# microcontroller.net
KiCad netlist of a schematic drawn in Altium Designer
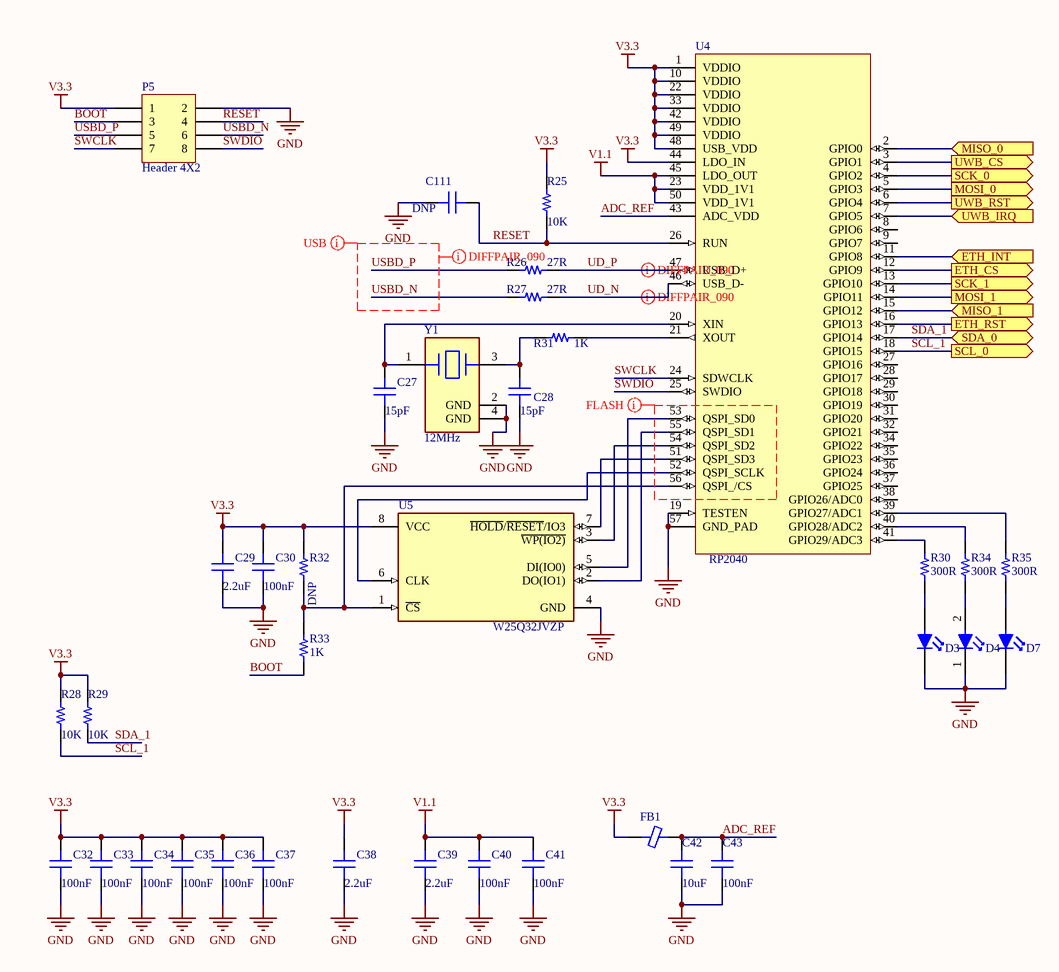
[diagram p0: microcontroller.SchDoc]

(export (version "E")
  (design (tool "Eeschema 10.0.6"))
  (components
    (comp (ref "C27")
      (value "15pF")
      (footprint "CAP 0603_1608")
      (description "SMT Capacitor")
      (fields (field (name "MF") "Murata") (field (name "MP") "GRM1885C1H150JA01J"))
      (libsource (lib "Capacitor") (part "Capacitor"))
    )
    (comp (ref "C28")
      (value "15pF")
      (footprint "CAP 0603_1608")
      (description "SMT Capacitor")
      (fields (field (name "MF") "Murata") (field (name "MP") "GRM1885C1H150JA01J"))
      (libsource (lib "Capacitor") (part "Capacitor"))
    )
    (comp (ref "C29")
      (value "2.2uF")
      (footprint "CAP 0603_1608")
      (description "SMT Capacitor")
      (fields (field (name "MF") "Samsung") (field (name "MP") "CL10A225KP8NNNC"))
      (libsource (lib "Capacitor") (part "Capacitor"))
    )
    (comp (ref "C30")
      (value "100nF")
      (footprint "CAP 0603_1608")
      (description "SMT Capacitor")
      (fields (field (name "MF") "TDK") (field (name "MP") "CGA3E2X7R1E104K080AA"))
      (libsource (lib "Capacitor") (part "Capacitor"))
    )
    (comp (ref "C32")
      (value "100nF")
      (footprint "CAP 0603_1608")
      (description "SMT Capacitor")
      (fields (field (name "MF") "TDK") (field (name "MP") "CGA3E2X7R1E104K080AA"))
      (libsource (lib "Capacitor") (part "Capacitor"))
    )
    (comp (ref "C33")
      (value "100nF")
      (footprint "CAP 0603_1608")
      (description "SMT Capacitor")
      (fields (field (name "MF") "TDK") (field (name "MP") "CGA3E2X7R1E104K080AA"))
      (libsource (lib "Capacitor") (part "Capacitor"))
    )
    (comp (ref "C34")
      (value "100nF")
      (footprint "CAP 0603_1608")
      (description "SMT Capacitor")
      (fields (field (name "MF") "TDK") (field (name "MP") "CGA3E2X7R1E104K080AA"))
      (libsource (lib "Capacitor") (part "Capacitor"))
    )
    (comp (ref "C35")
      (value "100nF")
      (footprint "CAP 0603_1608")
      (description "SMT Capacitor")
      (fields (field (name "MF") "TDK") (field (name "MP") "CGA3E2X7R1E104K080AA"))
      (libsource (lib "Capacitor") (part "Capacitor"))
    )
    (comp (ref "C36")
      (value "100nF")
      (footprint "CAP 0603_1608")
      (description "SMT Capacitor")
      (fields (field (name "MF") "TDK") (field (name "MP") "CGA3E2X7R1E104K080AA"))
      (libsource (lib "Capacitor") (part "Capacitor"))
    )
    (comp (ref "C37")
      (value "100nF")
      (footprint "CAP 0603_1608")
      (description "SMT Capacitor")
      (fields (field (name "MF") "TDK") (field (name "MP") "CGA3E2X7R1E104K080AA"))
      (libsource (lib "Capacitor") (part "Capacitor"))
    )
    (comp (ref "C38")
      (value "2.2uF")
      (footprint "CAP 0603_1608")
      (description "SMT Capacitor")
      (fields (field (name "MF") "Samsung") (field (name "MP") "CL10A225KP8NNNC"))
      (libsource (lib "Capacitor") (part "Capacitor"))
    )
    (comp (ref "C39")
      (value "2.2uF")
      (footprint "CAP 0603_1608")
      (description "SMT Capacitor")
      (fields (field (name "MF") "Samsung") (field (name "MP") "CL10A225KP8NNNC"))
      (libsource (lib "Capacitor") (part "Capacitor"))
    )
    (comp (ref "C40")
      (value "100nF")
      (footprint "CAP 0603_1608")
      (description "SMT Capacitor")
      (fields (field (name "MF") "TDK") (field (name "MP") "CGA3E2X7R1E104K080AA"))
      (libsource (lib "Capacitor") (part "Capacitor"))
    )
    (comp (ref "C41")
      (value "100nF")
      (footprint "CAP 0603_1608")
      (description "SMT Capacitor")
      (fields (field (name "MF") "TDK") (field (name "MP") "CGA3E2X7R1E104K080AA"))
      (libsource (lib "Capacitor") (part "Capacitor"))
    )
    (comp (ref "C42")
      (value "10uF")
      (footprint "CAP 0603_1608")
      (description "SMT Capacitor")
      (fields (field (name "MF") "Murata") (field (name "MP") "GRM188R61C106MAALD"))
      (libsource (lib "Capacitor") (part "Capacitor"))
    )
    (comp (ref "C43")
      (value "100nF")
      (footprint "CAP 0603_1608")
      (description "SMT Capacitor")
      (fields (field (name "MF") "TDK") (field (name "MP") "CGA3E2X7R1E104K080AA"))
      (libsource (lib "Capacitor") (part "Capacitor"))
    )
    (comp (ref "C111")
      (value "DNP")
      (footprint "CAP 0603_1608")
      (description "SMT Capacitor")
      (fields (field (name "MP") "C0603C104K4PACTU"))
      (libsource (lib "Capacitor") (part "Capacitor"))
    )
    (comp (ref "D3")
      (value "Green")
      (footprint "Würth_Elektronik_0_MFG")
      (description "Led Diffused SMD")
      (fields (field (name "MF") "LiteOn") (field (name "MP") "LTST-C190KGKT"))
      (libsource (lib "Diode") (part "LED SMD"))
    )
    (comp (ref "D4")
      (value "Red")
      (footprint "Würth_Elektronik_0_MFG")
      (description "Led Diffused SMD")
      (fields (field (name "MF") "LiteOn") (field (name "MP") "LTST-C190KRKT"))
      (libsource (lib "") (part "LED SMD_1"))
    )
    (comp (ref "D7")
      (value "Green")
      (footprint "Würth_Elektronik_0_MFG")
      (description "Led Diffused SMD")
      (fields (field (name "MF") "LiteOn") (field (name "MP") "LTST-C190KGKT"))
      (libsource (lib "Diode") (part "LED SMD"))
    )
    (comp (ref "FB1")
      (value "Ferrite Beads")
      (footprint "Murata_BLM18-0_15-t0_8_MFG")
      (description "SMT Ferrite Chip")
      (fields (field (name "MF") "Murata") (field (name "MP") "BLM18PG471SN1D"))
      (libsource (lib "Passive") (part "Ferrite Chip"))
    )
    (comp (ref "P5")
      (value "Header 4X2")
      (footprint "HDR2X4")
      (description "Header, 4-Pin, Dual row")
      (fields (field (name "PUBLISHER") "Altium Limited"))
      (libsource (lib "Connector") (part "Header 4X2"))
    )
    (comp (ref "R25")
      (value "10K")
      (footprint "RES 0603_1608")
      (description "SMT Resistor")
      (fields (field (name "MF") "YAGEO") (field (name "MP") "AC0603FR-0710KL"))
      (libsource (lib "Resistor") (part "Resistor"))
    )
    (comp (ref "R26")
      (value "27R")
      (footprint "RES 0603_1608")
      (description "SMT Resistor")
      (fields (field (name "MF") "YAGEO") (field (name "MP") "AC0603FR-0727RL"))
      (libsource (lib "Resistor") (part "Resistor"))
    )
    (comp (ref "R27")
      (value "27R")
      (footprint "RES 0603_1608")
      (description "SMT Resistor")
      (fields (field (name "MF") "YAGEO") (field (name "MP") "AC0603FR-0727RL"))
      (libsource (lib "Resistor") (part "Resistor"))
    )
    (comp (ref "R28")
      (value "10K")
      (footprint "RES 0603_1608")
      (description "SMT Resistor")
      (fields (field (name "MF") "YAGEO") (field (name "MP") "AC0603FR-0710KL"))
      (libsource (lib "Resistor") (part "Resistor"))
    )
    (comp (ref "R29")
      (value "10K")
      (footprint "RES 0603_1608")
      (description "SMT Resistor")
      (fields (field (name "MF") "YAGEO") (field (name "MP") "AC0603FR-0710KL"))
      (libsource (lib "Resistor") (part "Resistor"))
    )
    (comp (ref "R30")
      (value "300R")
      (footprint "RES 0603_1608")
      (description "SMT Resistor")
      (fields (field (name "MF") "YAGEO") (field (name "MP") "AC0603FR-07300RL"))
      (libsource (lib "Resistor") (part "Resistor"))
    )
    (comp (ref "R31")
      (value "1K")
      (footprint "RES 0603_1608")
      (description "SMT Resistor")
      (fields (field (name "MF") "YAGEO") (field (name "MP") "AC0603FR-071KL"))
      (libsource (lib "Resistor") (part "Resistor"))
    )
    (comp (ref "R32")
      (value "DNP")
      (footprint "RES 0603_1608")
      (description "SMT Resistor")
      (libsource (lib "Resistor") (part "Resistor"))
    )
    (comp (ref "R33")
      (value "1K")
      (footprint "RES 0603_1608")
      (description "SMT Resistor")
      (fields (field (name "MF") "YAGEO") (field (name "MP") "AC0603FR-071KL"))
      (libsource (lib "Resistor") (part "Resistor"))
    )
    (comp (ref "R34")
      (value "300R")
      (footprint "RES 0603_1608")
      (description "SMT Resistor")
      (fields (field (name "MF") "YAGEO") (field (name "MP") "AC0603FR-07300RL"))
      (libsource (lib "Resistor") (part "Resistor"))
    )
    (comp (ref "R35")
      (value "300R")
      (footprint "RES 0603_1608")
      (description "SMT Resistor")
      (fields (field (name "MF") "YAGEO") (field (name "MP") "AC0603FR-07300RL"))
      (libsource (lib "Resistor") (part "Resistor"))
    )
    (comp (ref "U4")
      (value "RP2040")
      (footprint "RP2040-Footprint-1")
      (fields (field (name "MF") "Raspberry Pi") (field (name "MP") "RP2040TR13"))
      (libsource (lib "RP2040") (part "RP2040"))
    )
    (comp (ref "U5")
      (value "W25Q32JVZP")
      (footprint "WINBOND WSON-8 6x5mm")
      (description "3V 32M-BIT SERIAL FLASH MEMORY WITH DUAL, QUAD SPI")
      (fields (field (name "MF") "Winbond") (field (name "MP") "W25Q32JVZPIQ"))
      (libsource (lib "Memory") (part "W25Q32JVZP"))
    )
    (comp (ref "Y1")
      (value "12MHz")
      (footprint "ABRACON ABM8G")
      (description "Crystals AEC-Q200 CRYSTAL 4pin SMD")
      (fields (field (name "MF") "ECS") (field (name "MP") "ECS-120-12-33-AGN-TR"))
      (libsource (lib "Crystal") (part "Crystal"))
    )
  )
  (nets
    (net (code "2") (name "/ADC_REF") (class "Default")
      (node (ref "C42") (pin "1") (pinfunction "1_1") (pintype "passive"))
      (node (ref "C43") (pin "1") (pinfunction "1_1") (pintype "passive"))
      (node (ref "FB1") (pin "2") (pinfunction "2_2") (pintype "passive"))
      (node (ref "U4") (pin "43") (pinfunction "ADC_VDD_43") (pintype "power_in"))
    )
    (net (code "3") (name "/BOOT") (class "Default")
      (node (ref "P5") (pin "3") (pinfunction "3_3") (pintype "passive"))
      (node (ref "R33") (pin "1") (pinfunction "1_1") (pintype "passive"))
    )
    (net (code "4") (name "/ETH_CS") (class "Default")
      (node (ref "U4") (pin "12") (pinfunction "GPIO9_12") (pintype "bidirectional"))
    )
    (net (code "5") (name "/ETH_INT") (class "Default")
      (node (ref "U4") (pin "11") (pinfunction "GPIO8_11") (pintype "bidirectional"))
    )
    (net (code "6") (name "/ETH_RST") (class "Default")
      (node (ref "U4") (pin "16") (pinfunction "GPIO13_16") (pintype "bidirectional"))
    )
    (net (code "7") (name "/MISO_0") (class "Default")
      (node (ref "U4") (pin "2") (pinfunction "GPIO0_2") (pintype "bidirectional"))
    )
    (net (code "8") (name "/MISO_1") (class "Default")
      (node (ref "U4") (pin "15") (pinfunction "GPIO12_15") (pintype "bidirectional"))
    )
    (net (code "9") (name "/MOSI_0") (class "Default")
      (node (ref "U4") (pin "5") (pinfunction "GPIO3_5") (pintype "bidirectional"))
    )
    (net (code "10") (name "/MOSI_1") (class "Default")
      (node (ref "U4") (pin "14") (pinfunction "GPIO11_14") (pintype "bidirectional"))
    )
    (net (code "11") (name "/RESET") (class "Default")
      (node (ref "C111") (pin "2") (pinfunction "2_2") (pintype "passive"))
      (node (ref "P5") (pin "4") (pinfunction "4_4") (pintype "passive"))
      (node (ref "R25") (pin "1") (pinfunction "1_1") (pintype "passive"))
      (node (ref "U4") (pin "26") (pinfunction "RUN_26") (pintype "input"))
    )
    (net (code "12") (name "/SCK_0") (class "Default")
      (node (ref "U4") (pin "4") (pinfunction "GPIO2_4") (pintype "bidirectional"))
    )
    (net (code "13") (name "/SCK_1") (class "Default")
      (node (ref "U4") (pin "13") (pinfunction "GPIO10_13") (pintype "bidirectional"))
    )
    (net (code "14") (name "/SCL_1") (class "Default")
      (node (ref "R28") (pin "1") (pinfunction "1_1") (pintype "passive"))
      (node (ref "U4") (pin "18") (pinfunction "GPIO15_18") (pintype "bidirectional"))
    )
    (net (code "15") (name "/SDA_1") (class "Default")
      (node (ref "R29") (pin "1") (pinfunction "1_1") (pintype "passive"))
      (node (ref "U4") (pin "17") (pinfunction "GPIO14_17") (pintype "bidirectional"))
    )
    (net (code "16") (name "/SWCLK") (class "Default")
      (node (ref "P5") (pin "7") (pinfunction "7_7") (pintype "passive"))
      (node (ref "U4") (pin "24") (pinfunction "SDWCLK_24") (pintype "input"))
    )
    (net (code "17") (name "/SWDIO") (class "Default")
      (node (ref "P5") (pin "8") (pinfunction "8_8") (pintype "passive"))
      (node (ref "U4") (pin "25") (pinfunction "SWDIO_25") (pintype "bidirectional"))
    )
    (net (code "18") (name "/UD_N") (class "Default")
      (node (ref "R27") (pin "2") (pinfunction "2_2") (pintype "passive"))
      (node (ref "U4") (pin "46") (pinfunction "USB_D-_46") (pintype "bidirectional"))
    )
    (net (code "19") (name "/UD_P") (class "Default")
      (node (ref "R26") (pin "2") (pinfunction "2_2") (pintype "passive"))
      (node (ref "U4") (pin "47") (pinfunction "USB_D+_47") (pintype "bidirectional"))
    )
    (net (code "20") (name "/USBD_N") (class "Default")
      (node (ref "P5") (pin "6") (pinfunction "6_6") (pintype "passive"))
      (node (ref "R27") (pin "1") (pinfunction "1_1") (pintype "passive"))
    )
    (net (code "21") (name "/USBD_P") (class "Default")
      (node (ref "P5") (pin "5") (pinfunction "5_5") (pintype "passive"))
      (node (ref "R26") (pin "1") (pinfunction "1_1") (pintype "passive"))
    )
    (net (code "22") (name "/UWB_CS") (class "Default")
      (node (ref "U4") (pin "3") (pinfunction "GPIO1_3") (pintype "bidirectional"))
    )
    (net (code "23") (name "/UWB_IRQ") (class "Default")
      (node (ref "U4") (pin "7") (pinfunction "GPIO5_7") (pintype "bidirectional"))
    )
    (net (code "24") (name "/UWB_RST") (class "Default")
      (node (ref "U4") (pin "6") (pinfunction "GPIO4_6") (pintype "bidirectional"))
    )
    (net (code "25") (name "GND") (class "Default")
      (node (ref "C111") (pin "1") (pinfunction "1_1") (pintype "passive"))
      (node (ref "C27") (pin "1") (pinfunction "1_1") (pintype "passive"))
      (node (ref "C28") (pin "1") (pinfunction "1_1") (pintype "passive"))
      (node (ref "C29") (pin "2") (pinfunction "2_2") (pintype "passive"))
      (node (ref "C30") (pin "2") (pinfunction "2_2") (pintype "passive"))
      (node (ref "C32") (pin "2") (pinfunction "2_2") (pintype "passive"))
      (node (ref "C33") (pin "2") (pinfunction "2_2") (pintype "passive"))
      (node (ref "C34") (pin "2") (pinfunction "2_2") (pintype "passive"))
      (node (ref "C35") (pin "2") (pinfunction "2_2") (pintype "passive"))
      (node (ref "C36") (pin "2") (pinfunction "2_2") (pintype "passive"))
      (node (ref "C37") (pin "2") (pinfunction "2_2") (pintype "passive"))
      (node (ref "C38") (pin "2") (pinfunction "2_2") (pintype "passive"))
      (node (ref "C39") (pin "2") (pinfunction "2_2") (pintype "passive"))
      (node (ref "C40") (pin "2") (pinfunction "2_2") (pintype "passive"))
      (node (ref "C41") (pin "2") (pinfunction "2_2") (pintype "passive"))
      (node (ref "C42") (pin "2") (pinfunction "2_2") (pintype "passive"))
      (node (ref "C43") (pin "2") (pinfunction "2_2") (pintype "passive"))
      (node (ref "D3") (pin "1") (pinfunction "C_1") (pintype "passive"))
      (node (ref "D4") (pin "1") (pinfunction "C_1") (pintype "passive"))
      (node (ref "D7") (pin "1") (pinfunction "C_1") (pintype "passive"))
      (node (ref "P5") (pin "2") (pinfunction "2_2") (pintype "passive"))
      (node (ref "U4") (pin "19") (pinfunction "TESTEN_19") (pintype "input"))
      (node (ref "U4") (pin "57") (pinfunction "GND_PAD_57") (pintype "power_in"))
      (node (ref "U5") (pin "4") (pinfunction "GND_4") (pintype "power_in"))
      (node (ref "Y1") (pin "2") (pinfunction "GND_2") (pintype "power_in"))
      (node (ref "Y1") (pin "4") (pinfunction "GND_4") (pintype "power_in"))
    )
    (net (code "26") (name "Net-(C28-Pad2)") (class "Default")
      (node (ref "C28") (pin "2") (pinfunction "2_2") (pintype "passive"))
      (node (ref "R31") (pin "1") (pinfunction "1_1") (pintype "passive"))
      (node (ref "Y1") (pin "3") (pinfunction "3_3") (pintype "passive"))
    )
    (net (code "27") (name "Net-(D3-A)") (class "Default")
      (node (ref "D3") (pin "2") (pinfunction "A_2") (pintype "passive"))
      (node (ref "R30") (pin "2") (pinfunction "2_2") (pintype "passive"))
    )
    (net (code "28") (name "Net-(D4-A)") (class "Default")
      (node (ref "D4") (pin "2") (pinfunction "A_2") (pintype "passive"))
      (node (ref "R34") (pin "2") (pinfunction "2_2") (pintype "passive"))
    )
    (net (code "29") (name "Net-(D7-A)") (class "Default")
      (node (ref "D7") (pin "2") (pinfunction "A_2") (pintype "passive"))
      (node (ref "R35") (pin "1") (pinfunction "1_1") (pintype "passive"))
    )
    (net (code "30") (name "Net-(U4-GPIO27{slash}ADC1)") (class "Default")
      (node (ref "R35") (pin "2") (pinfunction "2_2") (pintype "passive"))
      (node (ref "U4") (pin "39") (pinfunction "GPIO27/ADC1_39") (pintype "bidirectional"))
    )
    (net (code "31") (name "Net-(U4-GPIO28{slash}ADC2)") (class "Default")
      (node (ref "R34") (pin "1") (pinfunction "1_1") (pintype "passive"))
      (node (ref "U4") (pin "40") (pinfunction "GPIO28/ADC2_40") (pintype "bidirectional"))
    )
    (net (code "32") (name "Net-(U4-GPIO29{slash}ADC3)") (class "Default")
      (node (ref "R30") (pin "1") (pinfunction "1_1") (pintype "passive"))
      (node (ref "U4") (pin "41") (pinfunction "GPIO29/ADC3_41") (pintype "bidirectional"))
    )
    (net (code "33") (name "Net-(U4-QSPI_SCLK)") (class "Default")
      (node (ref "U4") (pin "52") (pinfunction "QSPI_SCLK_52") (pintype "bidirectional"))
      (node (ref "U5") (pin "6") (pinfunction "CLK_6") (pintype "input"))
    )
    (net (code "34") (name "Net-(U4-QSPI_SD0)") (class "Default")
      (node (ref "U4") (pin "53") (pinfunction "QSPI_SD0_53") (pintype "bidirectional"))
      (node (ref "U5") (pin "5") (pinfunction "DI(IO0)_5") (pintype "bidirectional"))
    )
    (net (code "35") (name "Net-(U4-QSPI_SD1)") (class "Default")
      (node (ref "U4") (pin "55") (pinfunction "QSPI_SD1_55") (pintype "bidirectional"))
      (node (ref "U5") (pin "2") (pinfunction "DO(IO1)_2") (pintype "bidirectional"))
    )
    (net (code "36") (name "Net-(U4-QSPI_SD2)") (class "Default")
      (node (ref "U4") (pin "54") (pinfunction "QSPI_SD2_54") (pintype "bidirectional"))
      (node (ref "U5") (pin "3") (pinfunction "~{WP(IO2)}_3") (pintype "bidirectional"))
    )
    (net (code "37") (name "Net-(U4-QSPI_SD3)") (class "Default")
      (node (ref "U4") (pin "51") (pinfunction "QSPI_SD3_51") (pintype "bidirectional"))
      (node (ref "U5") (pin "7") (pinfunction "~{HOLD}/~{RESET}/IO3_7") (pintype "bidirectional"))
    )
    (net (code "38") (name "Net-(U4-QSPI_{slash}CS)") (class "Default")
      (node (ref "R32") (pin "2") (pinfunction "2_2") (pintype "passive"))
      (node (ref "R33") (pin "2") (pinfunction "2_2") (pintype "passive"))
      (node (ref "U4") (pin "56") (pinfunction "QSPI_/CS_56") (pintype "bidirectional"))
      (node (ref "U5") (pin "1") (pinfunction "~{CS}_1") (pintype "input"))
    )
    (net (code "39") (name "Net-(U4-XIN)") (class "Default")
      (node (ref "C27") (pin "2") (pinfunction "2_2") (pintype "passive"))
      (node (ref "U4") (pin "20") (pinfunction "XIN_20") (pintype "input"))
      (node (ref "Y1") (pin "1") (pinfunction "1_1") (pintype "passive"))
    )
    (net (code "40") (name "Net-(U4-XOUT)") (class "Default")
      (node (ref "R31") (pin "2") (pinfunction "2_2") (pintype "passive"))
      (node (ref "U4") (pin "21") (pinfunction "XOUT_21") (pintype "output"))
    )
    (net (code "41") (name "V1.1") (class "Default")
      (node (ref "C39") (pin "1") (pinfunction "1_1") (pintype "passive"))
      (node (ref "C40") (pin "1") (pinfunction "1_1") (pintype "passive"))
      (node (ref "C41") (pin "1") (pinfunction "1_1") (pintype "passive"))
      (node (ref "U4") (pin "23") (pinfunction "VDD_1V1_23") (pintype "power_in"))
      (node (ref "U4") (pin "45") (pinfunction "LDO_OUT_45") (pintype "power_in"))
      (node (ref "U4") (pin "50") (pinfunction "VDD_1V1_50") (pintype "power_in"))
    )
    (net (code "42") (name "V3.3") (class "Default")
      (node (ref "C29") (pin "1") (pinfunction "1_1") (pintype "passive"))
      (node (ref "C30") (pin "1") (pinfunction "1_1") (pintype "passive"))
      (node (ref "C32") (pin "1") (pinfunction "1_1") (pintype "passive"))
      (node (ref "C33") (pin "1") (pinfunction "1_1") (pintype "passive"))
      (node (ref "C34") (pin "1") (pinfunction "1_1") (pintype "passive"))
      (node (ref "C35") (pin "1") (pinfunction "1_1") (pintype "passive"))
      (node (ref "C36") (pin "1") (pinfunction "1_1") (pintype "passive"))
      (node (ref "C37") (pin "1") (pinfunction "1_1") (pintype "passive"))
      (node (ref "C38") (pin "1") (pinfunction "1_1") (pintype "passive"))
      (node (ref "FB1") (pin "1") (pinfunction "1_1") (pintype "passive"))
      (node (ref "P5") (pin "1") (pinfunction "1_1") (pintype "passive"))
      (node (ref "R25") (pin "2") (pinfunction "2_2") (pintype "passive"))
      (node (ref "R28") (pin "2") (pinfunction "2_2") (pintype "passive"))
      (node (ref "R29") (pin "2") (pinfunction "2_2") (pintype "passive"))
      (node (ref "R32") (pin "1") (pinfunction "1_1") (pintype "passive"))
      (node (ref "U4") (pin "1") (pinfunction "VDDIO_1") (pintype "power_in"))
      (node (ref "U4") (pin "10") (pinfunction "VDDIO_10") (pintype "power_in"))
      (node (ref "U4") (pin "22") (pinfunction "VDDIO_22") (pintype "power_in"))
      (node (ref "U4") (pin "33") (pinfunction "VDDIO_33") (pintype "power_in"))
      (node (ref "U4") (pin "42") (pinfunction "VDDIO_42") (pintype "power_in"))
      (node (ref "U4") (pin "44") (pinfunction "LDO_IN_44") (pintype "power_in"))
      (node (ref "U4") (pin "48") (pinfunction "USB_VDD_48") (pintype "power_in"))
      (node (ref "U4") (pin "49") (pinfunction "VDDIO_49") (pintype "power_in"))
      (node (ref "U5") (pin "8") (pinfunction "VCC_8") (pintype "power_in"))
    )
    (net (code "43") (name "unconnected-(U4-GPIO6-Pad8)") (class "Default")
      (node (ref "U4") (pin "8") (pinfunction "GPIO6_8") (pintype "bidirectional"))
    )
    (net (code "44") (name "unconnected-(U4-GPIO7-Pad9)") (class "Default")
      (node (ref "U4") (pin "9") (pinfunction "GPIO7_9") (pintype "bidirectional"))
    )
    (net (code "45") (name "unconnected-(U4-GPIO16-Pad27)") (class "Default")
      (node (ref "U4") (pin "27") (pinfunction "GPIO16_27") (pintype "bidirectional"))
    )
    (net (code "46") (name "unconnected-(U4-GPIO17-Pad28)") (class "Default")
      (node (ref "U4") (pin "28") (pinfunction "GPIO17_28") (pintype "bidirectional"))
    )
    (net (code "47") (name "unconnected-(U4-GPIO18-Pad29)") (class "Default")
      (node (ref "U4") (pin "29") (pinfunction "GPIO18_29") (pintype "bidirectional"))
    )
    (net (code "48") (name "unconnected-(U4-GPIO19-Pad30)") (class "Default")
      (node (ref "U4") (pin "30") (pinfunction "GPIO19_30") (pintype "bidirectional"))
    )
    (net (code "49") (name "unconnected-(U4-GPIO20-Pad31)") (class "Default")
      (node (ref "U4") (pin "31") (pinfunction "GPIO20_31") (pintype "bidirectional"))
    )
    (net (code "50") (name "unconnected-(U4-GPIO21-Pad32)") (class "Default")
      (node (ref "U4") (pin "32") (pinfunction "GPIO21_32") (pintype "bidirectional"))
    )
    (net (code "51") (name "unconnected-(U4-GPIO22-Pad34)") (class "Default")
      (node (ref "U4") (pin "34") (pinfunction "GPIO22_34") (pintype "bidirectional"))
    )
    (net (code "52") (name "unconnected-(U4-GPIO23-Pad35)") (class "Default")
      (node (ref "U4") (pin "35") (pinfunction "GPIO23_35") (pintype "bidirectional"))
    )
    (net (code "53") (name "unconnected-(U4-GPIO24-Pad36)") (class "Default")
      (node (ref "U4") (pin "36") (pinfunction "GPIO24_36") (pintype "bidirectional"))
    )
    (net (code "54") (name "unconnected-(U4-GPIO25-Pad37)") (class "Default")
      (node (ref "U4") (pin "37") (pinfunction "GPIO25_37") (pintype "bidirectional"))
    )
    (net (code "55") (name "unconnected-(U4-GPIO26{slash}ADC0-Pad38)") (class "Default")
      (node (ref "U4") (pin "38") (pinfunction "GPIO26/ADC0_38") (pintype "bidirectional"))
    )
  )
)
